# motor_tester.net
KiCad netlist of a schematic drawn in EAGLE
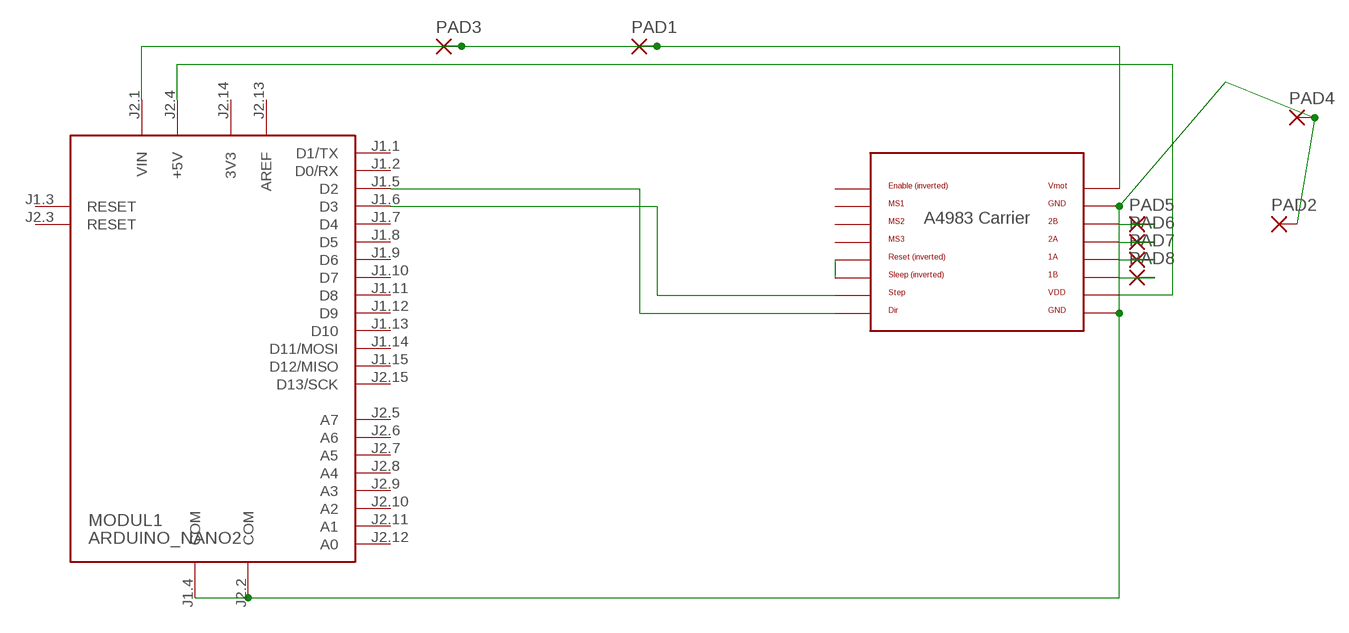
[diagram p0: schematic, sheet 1]

(export (version "E")
  (design (tool "Eeschema 10.0.6"))
  (components
    (comp (ref "MODUL1")
      (value "ARDUINO_NANO2")
      (footprint "eagle-import:ARDUINO_NANO2")
      (libsource (lib "eagle-import") (part "ARDUINO_NANO2"))
    )
    (comp (ref "PAD1")
      (value "1,6/0,8")
      (footprint "eagle-import:1,6_0,8")
      (libsource (lib "eagle-import") (part "1,6/0,8"))
    )
    (comp (ref "PAD2")
      (value "1,6/0,8")
      (footprint "eagle-import:1,6_0,8")
      (libsource (lib "eagle-import") (part "1,6/0,8"))
    )
    (comp (ref "PAD3")
      (value "1,6/0,8")
      (footprint "eagle-import:1,6_0,8")
      (libsource (lib "eagle-import") (part "1,6/0,8"))
    )
    (comp (ref "PAD4")
      (value "1,6/0,8")
      (footprint "eagle-import:1,6_0,8")
      (libsource (lib "eagle-import") (part "1,6/0,8"))
    )
    (comp (ref "PAD5")
      (value "1,6/0,8")
      (footprint "eagle-import:1,6_0,8")
      (libsource (lib "eagle-import") (part "1,6/0,8"))
    )
    (comp (ref "PAD6")
      (value "1,6/0,8")
      (footprint "eagle-import:1,6_0,8")
      (libsource (lib "eagle-import") (part "1,6/0,8"))
    )
    (comp (ref "PAD7")
      (value "1,6/0,8")
      (footprint "eagle-import:1,6_0,8")
      (libsource (lib "eagle-import") (part "1,6/0,8"))
    )
    (comp (ref "PAD8")
      (value "1,6/0,8")
      (footprint "eagle-import:1,6_0,8")
      (libsource (lib "eagle-import") (part "1,6/0,8"))
    )
    (comp (ref "U$6")
      (value "POLOLU_A4983CARRIER")
      (footprint "eagle-import:A4983CARRIER")
      (libsource (lib "eagle-import") (part "POLOLU_A4983CARRIER"))
    )
  )
  (nets
    (net (code "1") (name "3V3") (class "Default")
      (node (ref "MODUL1") (pin "J2.14") (pinfunction "3V3_J2.14") (pintype "power_in"))
    )
    (net (code "2") (name "AREF") (class "Default")
      (node (ref "MODUL1") (pin "J2.13") (pinfunction "AREF_J2.13") (pintype "power_in"))
    )
    (net (code "3") (name "Net-(MODUL1-+5V)") (class "Default")
      (node (ref "MODUL1") (pin "J2.4") (pinfunction "+5V_J2.4") (pintype "power_in"))
      (node (ref "U$6") (pin "VDD") (pinfunction "VDD_VDD") (pintype "power_in"))
    )
    (net (code "4") (name "Net-(MODUL1-D2)") (class "Default")
      (node (ref "MODUL1") (pin "J1.5") (pinfunction "D2_J1.5") (pintype "bidirectional"))
      (node (ref "U$6") (pin "DIR") (pinfunction "DIR_DIR") (pintype "input"))
    )
    (net (code "5") (name "Net-(MODUL1-D3)") (class "Default")
      (node (ref "MODUL1") (pin "J1.6") (pinfunction "D3_J1.6") (pintype "bidirectional"))
      (node (ref "U$6") (pin "STEP") (pinfunction "STEP_STEP") (pintype "input"))
    )
    (net (code "6") (name "Net-(MODUL1-VIN)") (class "Default")
      (node (ref "MODUL1") (pin "J2.1") (pinfunction "VIN_J2.1") (pintype "power_in"))
      (node (ref "PAD1") (pin "1") (pinfunction "P_1") (pintype "passive"))
      (node (ref "PAD3") (pin "1") (pinfunction "P_1") (pintype "passive"))
      (node (ref "U$6") (pin "VMOT") (pinfunction "VMOT_VMOT") (pintype "power_in"))
    )
    (net (code "7") (name "Net-(PAD2-P)") (class "Default")
      (node (ref "MODUL1") (pin "J1.4") (pinfunction "COM_J1.4") (pintype "power_in"))
      (node (ref "MODUL1") (pin "J2.2") (pinfunction "COM_J2.2") (pintype "power_in"))
      (node (ref "PAD2") (pin "1") (pinfunction "P_1") (pintype "passive"))
      (node (ref "PAD4") (pin "1") (pinfunction "P_1") (pintype "passive"))
      (node (ref "U$6") (pin "GND") (pinfunction "GND_GND") (pintype "power_in"))
      (node (ref "U$6") (pin "GND@0") (pinfunction "GND_GND@0") (pintype "power_in"))
    )
    (net (code "8") (name "Net-(PAD5-P)") (class "Default")
      (node (ref "PAD5") (pin "1") (pinfunction "P_1") (pintype "passive"))
      (node (ref "U$6") (pin "2B") (pinfunction "2B_2B") (pintype "output"))
    )
    (net (code "9") (name "Net-(PAD6-P)") (class "Default")
      (node (ref "PAD6") (pin "1") (pinfunction "P_1") (pintype "passive"))
      (node (ref "U$6") (pin "2A") (pinfunction "2A_2A") (pintype "output"))
    )
    (net (code "10") (name "Net-(PAD7-P)") (class "Default")
      (node (ref "PAD7") (pin "1") (pinfunction "P_1") (pintype "passive"))
      (node (ref "U$6") (pin "1A") (pinfunction "1A_1A") (pintype "output"))
    )
    (net (code "11") (name "Net-(PAD8-P)") (class "Default")
      (node (ref "PAD8") (pin "1") (pinfunction "P_1") (pintype "passive"))
      (node (ref "U$6") (pin "1B") (pinfunction "1B_1B") (pintype "output"))
    )
    (net (code "12") (name "Net-(U$6-SLEEP)") (class "Default")
      (node (ref "U$6") (pin "RST") (pinfunction "RST_RST") (pintype "input"))
      (node (ref "U$6") (pin "SLP") (pinfunction "SLEEP_SLP") (pintype "input"))
    )
    (net (code "13") (name "unconnected-(MODUL1-A0-PadJ2.12)") (class "Default")
      (node (ref "MODUL1") (pin "J2.12") (pinfunction "A0_J2.12") (pintype "bidirectional"))
    )
    (net (code "14") (name "unconnected-(MODUL1-A1-PadJ2.11)") (class "Default")
      (node (ref "MODUL1") (pin "J2.11") (pinfunction "A1_J2.11") (pintype "bidirectional"))
    )
    (net (code "15") (name "unconnected-(MODUL1-A2-PadJ2.10)") (class "Default")
      (node (ref "MODUL1") (pin "J2.10") (pinfunction "A2_J2.10") (pintype "bidirectional"))
    )
    (net (code "16") (name "unconnected-(MODUL1-A3-PadJ2.9)") (class "Default")
      (node (ref "MODUL1") (pin "J2.9") (pinfunction "A3_J2.9") (pintype "bidirectional"))
    )
    (net (code "17") (name "unconnected-(MODUL1-A4-PadJ2.8)") (class "Default")
      (node (ref "MODUL1") (pin "J2.8") (pinfunction "A4_J2.8") (pintype "bidirectional"))
    )
    (net (code "18") (name "unconnected-(MODUL1-A5-PadJ2.7)") (class "Default")
      (node (ref "MODUL1") (pin "J2.7") (pinfunction "A5_J2.7") (pintype "bidirectional"))
    )
    (net (code "19") (name "unconnected-(MODUL1-A6-PadJ2.6)") (class "Default")
      (node (ref "MODUL1") (pin "J2.6") (pinfunction "A6_J2.6") (pintype "bidirectional"))
    )
    (net (code "20") (name "unconnected-(MODUL1-A7-PadJ2.5)") (class "Default")
      (node (ref "MODUL1") (pin "J2.5") (pinfunction "A7_J2.5") (pintype "bidirectional"))
    )
    (net (code "21") (name "unconnected-(MODUL1-D0{slash}RX-PadJ1.2)") (class "Default")
      (node (ref "MODUL1") (pin "J1.2") (pinfunction "D0/RX_J1.2") (pintype "bidirectional"))
    )
    (net (code "22") (name "unconnected-(MODUL1-D1{slash}TX-PadJ1.1)") (class "Default")
      (node (ref "MODUL1") (pin "J1.1") (pinfunction "D1/TX_J1.1") (pintype "bidirectional"))
    )
    (net (code "23") (name "unconnected-(MODUL1-D4-PadJ1.7)") (class "Default")
      (node (ref "MODUL1") (pin "J1.7") (pinfunction "D4_J1.7") (pintype "bidirectional"))
    )
    (net (code "24") (name "unconnected-(MODUL1-D5-PadJ1.8)") (class "Default")
      (node (ref "MODUL1") (pin "J1.8") (pinfunction "D5_J1.8") (pintype "bidirectional"))
    )
    (net (code "25") (name "unconnected-(MODUL1-D6-PadJ1.9)") (class "Default")
      (node (ref "MODUL1") (pin "J1.9") (pinfunction "D6_J1.9") (pintype "bidirectional"))
    )
    (net (code "26") (name "unconnected-(MODUL1-D7-PadJ1.10)") (class "Default")
      (node (ref "MODUL1") (pin "J1.10") (pinfunction "D7_J1.10") (pintype "bidirectional"))
    )
    (net (code "27") (name "unconnected-(MODUL1-D8-PadJ1.11)") (class "Default")
      (node (ref "MODUL1") (pin "J1.11") (pinfunction "D8_J1.11") (pintype "bidirectional"))
    )
    (net (code "28") (name "unconnected-(MODUL1-D9-PadJ1.12)") (class "Default")
      (node (ref "MODUL1") (pin "J1.12") (pinfunction "D9_J1.12") (pintype "bidirectional"))
    )
    (net (code "29") (name "unconnected-(MODUL1-D10-PadJ1.13)") (class "Default")
      (node (ref "MODUL1") (pin "J1.13") (pinfunction "D10_J1.13") (pintype "bidirectional"))
    )
    (net (code "30") (name "unconnected-(MODUL1-D11{slash}MOSI-PadJ1.14)") (class "Default")
      (node (ref "MODUL1") (pin "J1.14") (pinfunction "D11/MOSI_J1.14") (pintype "bidirectional"))
    )
    (net (code "31") (name "unconnected-(MODUL1-D12{slash}MISO-PadJ1.15)") (class "Default")
      (node (ref "MODUL1") (pin "J1.15") (pinfunction "D12/MISO_J1.15") (pintype "bidirectional"))
    )
    (net (code "32") (name "unconnected-(MODUL1-D13{slash}SCK-PadJ2.15)") (class "Default")
      (node (ref "MODUL1") (pin "J2.15") (pinfunction "D13/SCK_J2.15") (pintype "bidirectional"))
    )
    (net (code "33") (name "unconnected-(MODUL1-RESET-PadJ1.3)") (class "Default")
      (node (ref "MODUL1") (pin "J1.3") (pinfunction "RESET_J1.3") (pintype "bidirectional"))
    )
    (net (code "34") (name "unconnected-(MODUL1-RESET-PadJ2.3)") (class "Default")
      (node (ref "MODUL1") (pin "J2.3") (pinfunction "RESET_J2.3") (pintype "bidirectional"))
    )
    (net (code "35") (name "unconnected-(U$6-PadEN)") (class "Default")
      (node (ref "U$6") (pin "EN") (pinfunction "EN_EN") (pintype "input"))
    )
    (net (code "36") (name "unconnected-(U$6-PadMS1)") (class "Default")
      (node (ref "U$6") (pin "MS1") (pinfunction "MS1_MS1") (pintype "input"))
    )
    (net (code "37") (name "unconnected-(U$6-PadMS2)") (class "Default")
      (node (ref "U$6") (pin "MS2") (pinfunction "MS2_MS2") (pintype "input"))
    )
    (net (code "38") (name "unconnected-(U$6-PadMS3)") (class "Default")
      (node (ref "U$6") (pin "MS3") (pinfunction "MS3_MS3") (pintype "input"))
    )
  )
)
